# LPCB235_-_OPTONCDT_-_GROUP_A.net
KiCad netlist of a schematic drawn in Altium Designer
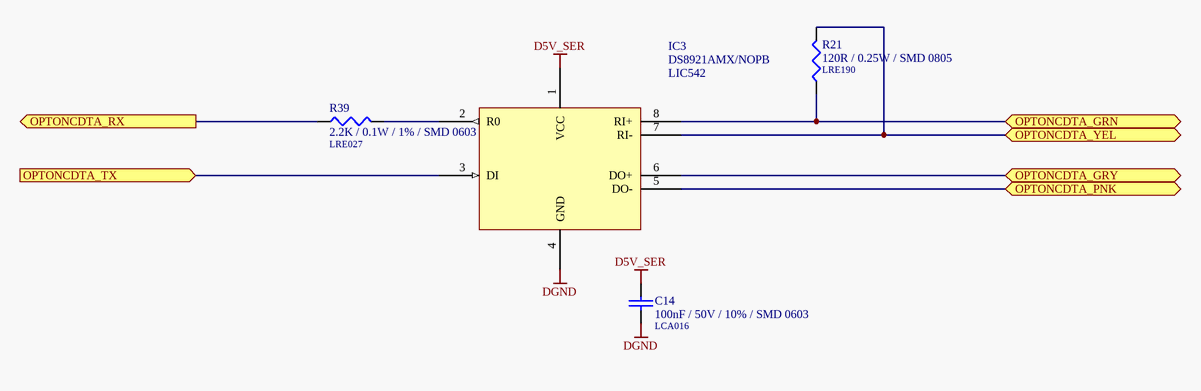
[diagram p0: LPCB235 - OPTONCDT - GROUP A.SchDoc]

(export (version "E")
  (design (tool "Eeschema 10.0.6"))
  (components
    (comp (ref "C14")
      (value "100nF / 50V / 10% / SMD 0603")
      (footprint "LFP011__CC1608-0603-IPC7351_B")
      (description "Capacitor, Ceramic Chip, 100nF (0.1uF), 50V, 5%, SMD 0603 [LCA016]")
      (fields (field (name "LDL_NUMBER") "LCA016"))
      (libsource (lib "LDL_Capacitors") (part "100nF / 50V / 10% / SMD 0603"))
    )
    (comp (ref "IC3")
      (value "DS8921AMX/NOPB")
      (footprint "LFP069__R-8G")
      (description "IC, RS422 Tx Rx, SMD SOIC 8")
      (fields (field (name "LDL_NUMBER") "LIC542"))
      (libsource (lib "LDL_Semiconductors") (part "DS8921AMX/NOPB"))
    )
    (comp (ref "R21")
      (value "120R / 0.25W / SMD 0805")
      (footprint "LFP029__CR2012-0805")
      (description "Resistor, Thick Film, 120R, 0.25W, 5%, SMD 0805 [LRE190]")
      (fields (field (name "LDL_NUMBER") "LRE190"))
      (libsource (lib "LDL_Resistors") (part "120R / 0.25W / SMD 0805"))
    )
    (comp (ref "R39")
      (value "2.2K / 0.1W / 1% / SMD 0603")
      (footprint "LFP020__CR1608-0603-IPC7351_B")
      (description "Resistor, Ceramic Chip, 2.2K, 0.1W, 1%, SMD 0603 [LRE027]")
      (fields (field (name "LDL_NUMBER") "LRE027"))
      (libsource (lib "LDL_Resistors") (part "2.2K / 0.1W / 1% / SMD 0603"))
    )
  )
  (nets
    (net (code "1") (name "/OPTONCDTA_GRN") (class "Default")
      (node (ref "IC3") (pin "8") (pinfunction "RI+_8") (pintype "passive"))
      (node (ref "R21") (pin "1") (pintype "passive"))
    )
    (net (code "2") (name "/OPTONCDTA_GRY") (class "Default")
      (node (ref "IC3") (pin "6") (pinfunction "DO+_6") (pintype "passive"))
    )
    (net (code "3") (name "/OPTONCDTA_PNK") (class "Default")
      (node (ref "IC3") (pin "5") (pinfunction "DO-_5") (pintype "passive"))
    )
    (net (code "4") (name "/OPTONCDTA_RX") (class "Default") (node (ref "R39") (pin "1") (pintype "passive")))
    (net (code "5") (name "/OPTONCDTA_TX") (class "Default")
      (node (ref "IC3") (pin "3") (pinfunction "DI_3") (pintype "input"))
    )
    (net (code "6") (name "/OPTONCDTA_YEL") (class "Default")
      (node (ref "IC3") (pin "7") (pinfunction "RI-_7") (pintype "passive"))
      (node (ref "R21") (pin "2") (pintype "passive"))
    )
    (net (code "7") (name "D5V_SER") (class "Default")
      (node (ref "C14") (pin "1") (pintype "passive"))
      (node (ref "IC3") (pin "1") (pinfunction "VCC_1") (pintype "power_in"))
    )
    (net (code "8") (name "DGND") (class "Default")
      (node (ref "C14") (pin "2") (pintype "passive"))
      (node (ref "IC3") (pin "4") (pinfunction "GND_4") (pintype "power_in"))
    )
    (net (code "9") (name "Net-(IC3-R0)") (class "Default")
      (node (ref "IC3") (pin "2") (pinfunction "R0_2") (pintype "output"))
      (node (ref "R39") (pin "2") (pintype "passive"))
    )
  )
)
